# PROC010B_QSPI_Flash_Reference.net
KiCad netlist of a schematic drawn in Altium Designer
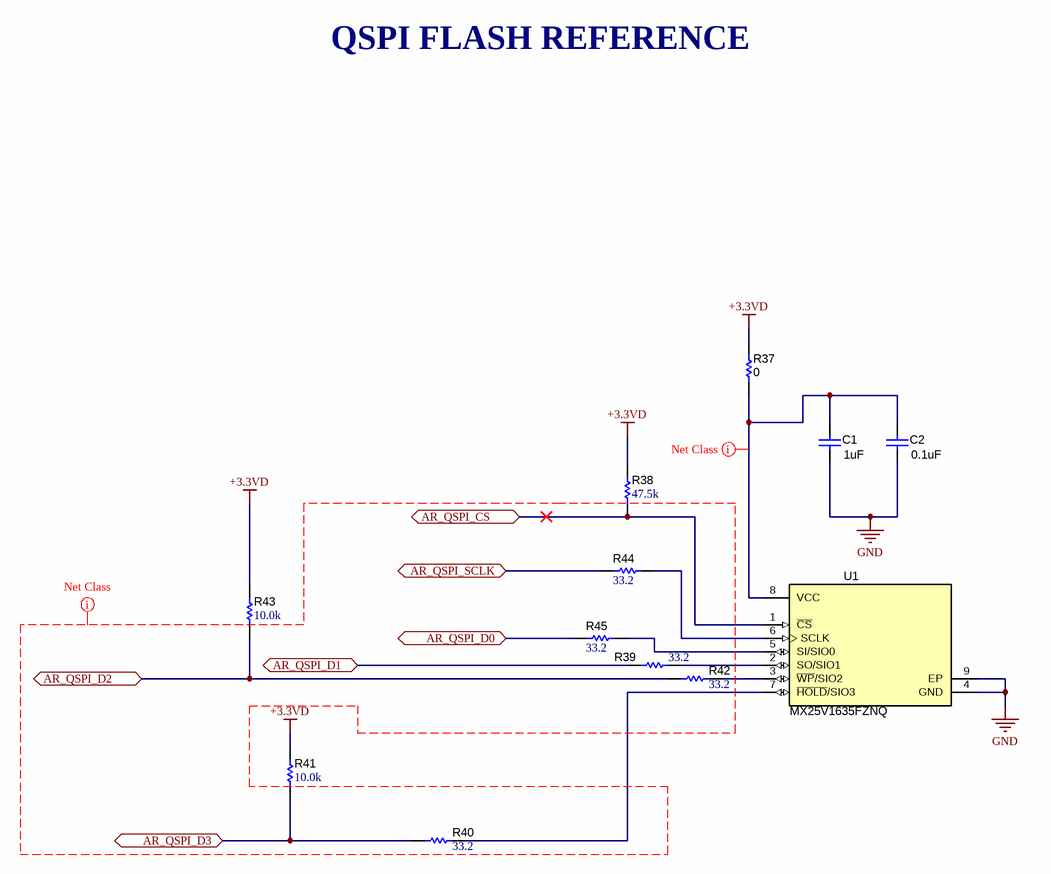
[diagram p0: PROC010B_QSPI_Flash_Reference.SchDoc]

(export (version "E")
  (design (tool "Eeschema 10.0.6"))
  (components
    (comp (ref "C1")
      (value "GCM188R71C105KA64D")
      (footprint "0603")
      (description "CAP, CERM, 1 uF, 16 V, +/- 10%, X7R, AEC-Q200 Grade 1, 0603")
      (fields
        (field (name "MANUFACTURER") "MuRata")
        (field (name "VALUEDISPLAYED") "1uF")
        (field (name "PUBLISHER") "Texas Instruments")
      )
      (libsource (lib "Altium Vault - TI") (part "Capacitor"))
    )
    (comp (ref "C2")
      (value "CGA2B3X7R1H104K050BB")
      (footprint "0402L")
      (description "CAP, CERM, 0.1 uF, 50 V, +/- 10%, X7R, AEC-Q200 Grade 1, 0402")
      (fields
        (field (name "MANUFACTURER") "TDK")
        (field (name "VALUEDISPLAYED") "0.1uF")
        (field (name "PUBLISHER") "Texas Instruments")
      )
      (libsource (lib "Altium Vault - TI") (part "Capacitor"))
    )
    (comp (ref "R37")
      (value "ERJ-2GE0R00X")
      (footprint "0402L")
      (description "RES, 0, 5%, 0.063 W, 0402")
      (fields
        (field (name "MANUFACTURER") "Panasonic")
        (field (name "VALUEDISPLAYED") "0")
        (field (name "PUBLISHER") "Texas Instruments")
      )
      (libsource (lib "Altium Vault - TI") (part "Resistor"))
    )
    (comp (ref "R38")
      (value "CRCW040247K5FKED")
      (footprint "0402L")
      (description "RES, 47.5 k, 1%, 0.063 W, AEC-Q200 Grade 0, 0402")
      (fields (field (name "MANUFACTURER") "Vishay-Dale") (field (name "VALUEDISPLAYED") "47.5k"))
      (libsource (lib "Altium Vault - TI") (part "Resistor"))
    )
    (comp (ref "R39")
      (value "CRCW020133R2FNED")
      (footprint "0201_Silk")
      (description "RES, 33.2, 1%, 0.05 W, 0201")
      (fields (field (name "MANUFACTURER") "Vishay-Dale") (field (name "VALUEDISPLAYED") "33.2"))
      (libsource (lib "Altium Vault - TI") (part "Resistor"))
    )
    (comp (ref "R40")
      (value "CRCW020133R2FNED")
      (footprint "0201_Silk")
      (description "RES, 33.2, 1%, 0.05 W, 0201")
      (fields (field (name "MANUFACTURER") "Vishay-Dale") (field (name "VALUEDISPLAYED") "33.2"))
      (libsource (lib "Altium Vault - TI") (part "Resistor"))
    )
    (comp (ref "R41")
      (value "CRCW040210K0FKED")
      (footprint "0402L")
      (description "RES, 10.0 k, 1%, 0.063 W, AEC-Q200 Grade 0, 0402")
      (fields (field (name "MANUFACTURER") "Vishay-Dale") (field (name "VALUEDISPLAYED") "10.0k"))
      (libsource (lib "Altium Vault - TI") (part "Resistor"))
    )
    (comp (ref "R42")
      (value "CRCW020133R2FNED")
      (footprint "0201_Silk")
      (description "RES, 33.2, 1%, 0.05 W, 0201")
      (fields (field (name "MANUFACTURER") "Vishay-Dale") (field (name "VALUEDISPLAYED") "33.2"))
      (libsource (lib "Altium Vault - TI") (part "Resistor"))
    )
    (comp (ref "R43")
      (value "CRCW040210K0FKED")
      (footprint "0402L")
      (description "RES, 10.0 k, 1%, 0.063 W, AEC-Q200 Grade 0, 0402")
      (fields (field (name "MANUFACTURER") "Vishay-Dale") (field (name "VALUEDISPLAYED") "10.0k"))
      (libsource (lib "Altium Vault - TI") (part "Resistor"))
    )
    (comp (ref "R44")
      (value "CRCW020133R2FNED")
      (footprint "0201_Silk")
      (description "RES, 33.2, 1%, 0.05 W, 0201")
      (fields (field (name "MANUFACTURER") "Vishay-Dale") (field (name "VALUEDISPLAYED") "33.2"))
      (libsource (lib "Altium Vault - TI") (part "Resistor"))
    )
    (comp (ref "R45")
      (value "CRCW020133R2FNED")
      (footprint "0201_Silk")
      (description "RES, 33.2, 1%, 0.05 W, 0201")
      (fields (field (name "MANUFACTURER") "Vishay-Dale") (field (name "VALUEDISPLAYED") "33.2"))
      (libsource (lib "Altium Vault - TI") (part "Resistor"))
    )
    (comp (ref "U1")
      (value "MX25V1635FZNQ")
      (footprint "WSON-8L_6x5MM_EP")
      (description "2.3V-3.6V, 16M-BIT [x 1/x 2/x 4] CMOS FLASH Memory, WSON-8")
      (fields (field (name "MANUFACTURER") "Macronix International Co., LTD"))
      (libsource (lib "Altium Vault - TI") (part "MX25V1635FZ"))
    )
  )
  (nets
    (net (code "1") (name "+3.3VD") (class "Default")
      (node (ref "R37") (pin "1") (pinfunction "1_1") (pintype "passive"))
      (node (ref "R38") (pin "2") (pinfunction "2_2") (pintype "passive"))
      (node (ref "R41") (pin "2") (pinfunction "2_2") (pintype "passive"))
      (node (ref "R43") (pin "2") (pinfunction "2_2") (pintype "passive"))
    )
    (net (code "2") (name "/AR_QSPI_CS") (class "Default")
      (node (ref "R38") (pin "1") (pinfunction "1_1") (pintype "passive"))
      (node (ref "U1") (pin "1") (pinfunction "CS_1") (pintype "input"))
    )
    (net (code "3") (name "/AR_QSPI_D0") (class "Default")
      (node (ref "R45") (pin "2") (pinfunction "2_2") (pintype "passive"))
    )
    (net (code "4") (name "/AR_QSPI_D1") (class "Default")
      (node (ref "R39") (pin "1") (pinfunction "1_1") (pintype "passive"))
    )
    (net (code "5") (name "/AR_QSPI_D2") (class "Default")
      (node (ref "R42") (pin "1") (pinfunction "1_1") (pintype "passive"))
      (node (ref "R43") (pin "1") (pinfunction "1_1") (pintype "passive"))
    )
    (net (code "6") (name "/AR_QSPI_D3") (class "Default")
      (node (ref "R40") (pin "2") (pinfunction "2_2") (pintype "passive"))
      (node (ref "R41") (pin "1") (pinfunction "1_1") (pintype "passive"))
    )
    (net (code "7") (name "/AR_QSPI_SCLK") (class "Default")
      (node (ref "R44") (pin "2") (pinfunction "2_2") (pintype "passive"))
    )
    (net (code "8") (name "GND") (class "Default")
      (node (ref "C1") (pin "1") (pinfunction "1_1") (pintype "passive"))
      (node (ref "C2") (pin "1") (pinfunction "1_1") (pintype "passive"))
      (node (ref "U1") (pin "4") (pinfunction "GND_4") (pintype "power_in"))
      (node (ref "U1") (pin "9") (pinfunction "EP_9") (pintype "passive"))
    )
    (net (code "9") (name "Net-(U1-SCLK)") (class "Default")
      (node (ref "R44") (pin "1") (pinfunction "1_1") (pintype "passive"))
      (node (ref "U1") (pin "6") (pinfunction "SCLK_6") (pintype "input"))
    )
    (net (code "10") (name "Net-(U1-SI{slash}SIO0)") (class "Default")
      (node (ref "R45") (pin "1") (pinfunction "1_1") (pintype "passive"))
      (node (ref "U1") (pin "5") (pinfunction "SI/SIO0_5") (pintype "bidirectional"))
    )
    (net (code "11") (name "Net-(U1-SO{slash}SIO1)") (class "Default")
      (node (ref "R39") (pin "2") (pinfunction "2_2") (pintype "passive"))
      (node (ref "U1") (pin "2") (pinfunction "SO/SIO1_2") (pintype "bidirectional"))
    )
    (net (code "12") (name "Net-(U1-VCC)") (class "Default")
      (node (ref "C1") (pin "2") (pinfunction "2_2") (pintype "passive"))
      (node (ref "C2") (pin "2") (pinfunction "2_2") (pintype "passive"))
      (node (ref "R37") (pin "2") (pinfunction "2_2") (pintype "passive"))
      (node (ref "U1") (pin "8") (pinfunction "VCC_8") (pintype "power_in"))
    )
    (net (code "13") (name "Net-(U1-~{HOLD}{slash}SIO3)") (class "Default")
      (node (ref "R40") (pin "1") (pinfunction "1_1") (pintype "passive"))
      (node (ref "U1") (pin "7") (pinfunction "~{HOLD}/SIO3_7") (pintype "bidirectional"))
    )
    (net (code "14") (name "Net-(U1-~{WP}{slash}SIO2)") (class "Default")
      (node (ref "R42") (pin "2") (pinfunction "2_2") (pintype "passive"))
      (node (ref "U1") (pin "3") (pinfunction "~{WP}/SIO2_3") (pintype "bidirectional"))
    )
  )
)
